# CW308T_ATSAMR21_Micro.net
KiCad netlist of a schematic drawn in Altium Designer
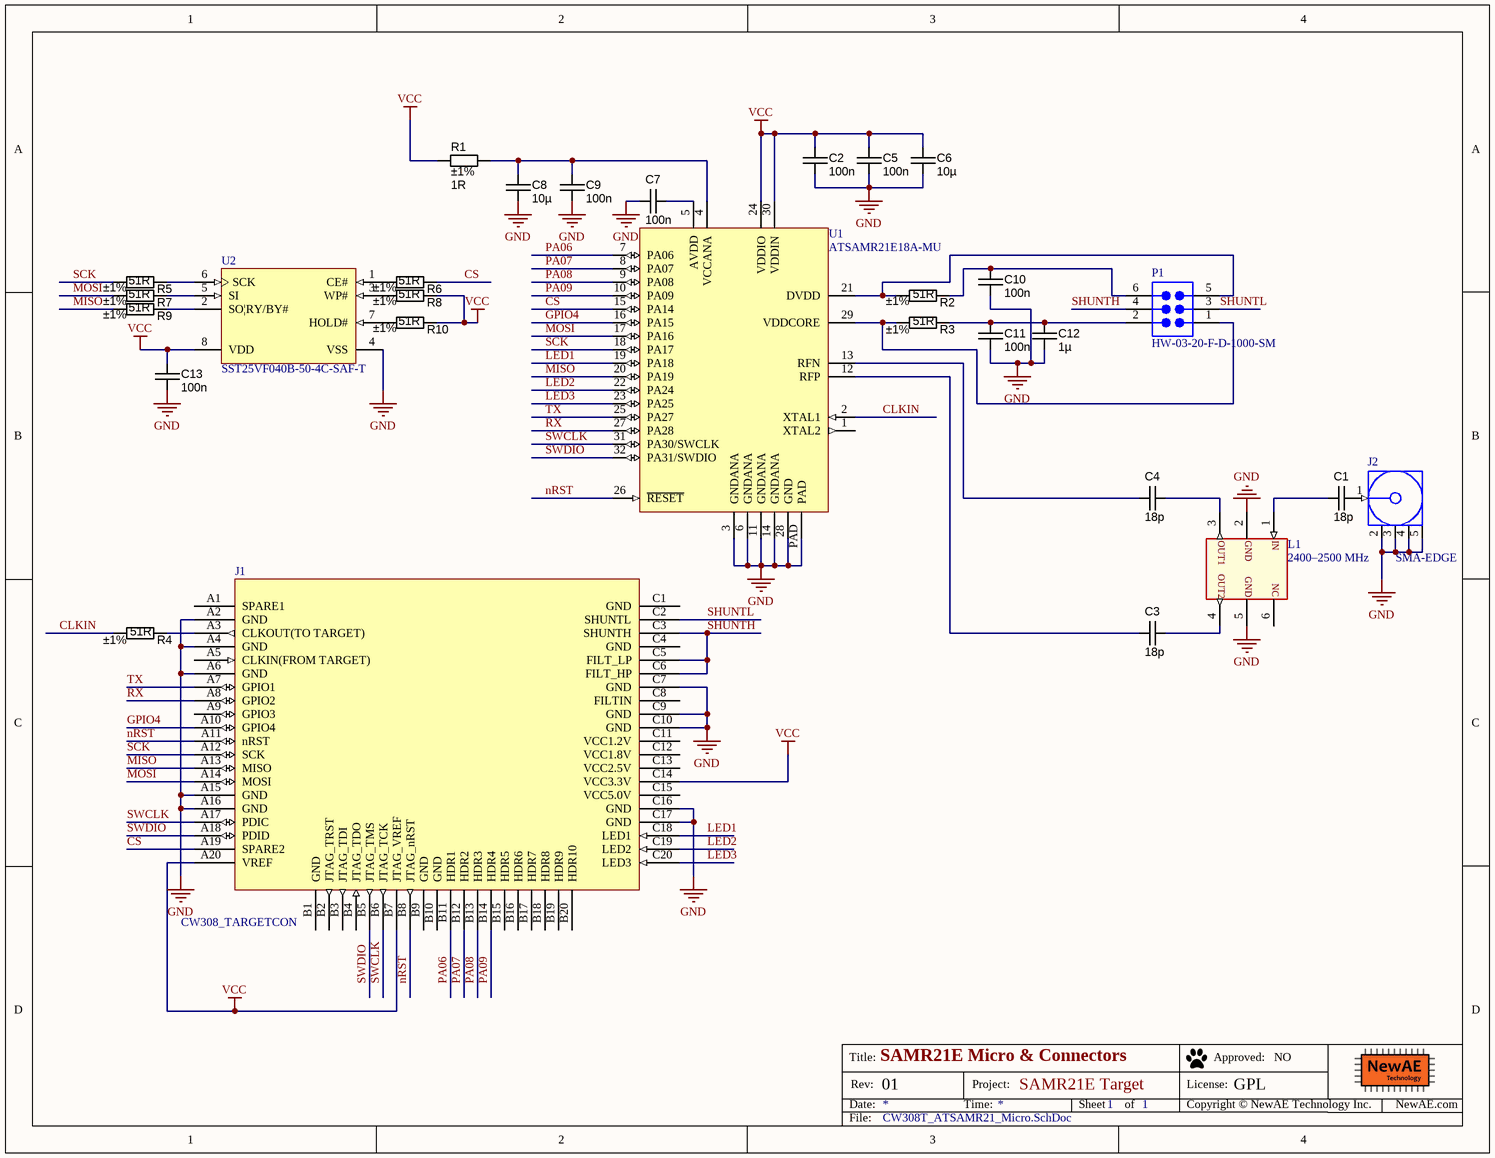
[diagram p0: CW308T_ATSAMR21_Micro.SchDoc]

(export (version "E")
  (design (tool "Eeschema 10.0.6"))
  (components
    (comp (ref "C1")
      (value "18p")
      (footprint "CAPC1608X90N")
      (description "Capacitor SMD Cer 18pF 2% 100V NP0 0603")
      (fields (field (name "TOLERANCE") "±2%"))
      (libsource (lib "PBL - Capacitors") (part "CAPC_18p_0603_100V"))
    )
    (comp (ref "C2")
      (value "100n")
      (footprint "CAPC1608X90N")
      (description "Capacitor SMD Cer 100nF 10% 50V X7R 0603")
      (fields (field (name "TOLERANCE") "±10%") (field (name "Comment") "approved sub OK"))
      (libsource (lib "PBL - Capacitors") (part "CAPC_100n_0603_X7R_50V_10%"))
    )
    (comp (ref "C3")
      (value "18p")
      (footprint "CAPC1608X90N")
      (description "Capacitor SMD Cer 18pF 2% 100V NP0 0603")
      (fields (field (name "TOLERANCE") "±2%"))
      (libsource (lib "PBL - Capacitors") (part "CAPC_18p_0603_100V"))
    )
    (comp (ref "C4")
      (value "18p")
      (footprint "CAPC1608X90N")
      (description "Capacitor SMD Cer 18pF 2% 100V NP0 0603")
      (fields (field (name "TOLERANCE") "±2%"))
      (libsource (lib "PBL - Capacitors") (part "CAPC_18p_0603_100V"))
    )
    (comp (ref "C5")
      (value "100n")
      (footprint "CAPC1608X90N")
      (description "Capacitor SMD Cer 100nF 10% 50V X7R 0603")
      (fields (field (name "TOLERANCE") "±10%") (field (name "Comment") "approved sub OK"))
      (libsource (lib "PBL - Capacitors") (part "CAPC_100n_0603_X7R_50V_10%"))
    )
    (comp (ref "C6")
      (value "10µ")
      (footprint "CAPC1608X90N")
      (description "Capacitor SMD Cer 10uF 10% 10V X5R 0603")
      (fields (field (name "TOLERANCE") "±10%") (field (name "Comment") "approved sub OK"))
      (libsource (lib "PBL - Capacitors") (part "CAPC_10u_0603_6V3"))
    )
    (comp (ref "C7")
      (value "100n")
      (footprint "CAPC1608X90N")
      (description "Capacitor SMD Cer 100nF 10% 50V X7R 0603")
      (fields (field (name "TOLERANCE") "±10%") (field (name "Comment") "approved sub OK"))
      (libsource (lib "PBL - Capacitors") (part "CAPC_100n_0603_X7R_50V_10%"))
    )
    (comp (ref "C8")
      (value "10µ")
      (footprint "CAPC1608X90N")
      (description "Capacitor SMD Cer 10uF 10% 10V X5R 0603")
      (fields (field (name "TOLERANCE") "±10%") (field (name "Comment") "approved sub OK"))
      (libsource (lib "PBL - Capacitors") (part "CAPC_10u_0603_6V3"))
    )
    (comp (ref "C9")
      (value "100n")
      (footprint "CAPC1608X90N")
      (description "Capacitor SMD Cer 100nF 10% 50V X7R 0603")
      (fields (field (name "TOLERANCE") "±10%") (field (name "Comment") "approved sub OK"))
      (libsource (lib "PBL - Capacitors") (part "CAPC_100n_0603_X7R_50V_10%"))
    )
    (comp (ref "C10")
      (value "100n")
      (footprint "CAPC1608X90N")
      (description "Capacitor SMD Cer 100nF 10% 50V X7R 0603")
      (fields (field (name "TOLERANCE") "±10%") (field (name "Comment") "approved sub OK"))
      (libsource (lib "PBL - Capacitors") (part "CAPC_100n_0603_X7R_50V_10%"))
    )
    (comp (ref "C11")
      (value "100n")
      (footprint "CAPC1608X90N")
      (description "Capacitor SMD Cer 100nF 10% 50V X7R 0603")
      (fields (field (name "TOLERANCE") "±10%") (field (name "Comment") "approved sub OK"))
      (libsource (lib "PBL - Capacitors") (part "CAPC_100n_0603_X7R_50V_10%"))
    )
    (comp (ref "C12")
      (value "1µ")
      (footprint "CAPC1608X90N")
      (description "Capacitor SMD Cer 1uF 10% 16V X7R 0603")
      (fields (field (name "TOLERANCE") "±10%") (field (name "Comment") "approved sub OK"))
      (libsource (lib "PBL - Capacitors") (part "CAPC_1u_0603_X7R_16V_10%"))
    )
    (comp (ref "C13")
      (value "100n")
      (footprint "CAPC1608X90N")
      (description "Capacitor SMD Cer 100nF 10% 50V X7R 0603")
      (fields (field (name "TOLERANCE") "±10%") (field (name "Comment") "approved sub OK"))
      (libsource (lib "PBL - Capacitors") (part "CAPC_100n_0603_X7R_50V_10%"))
    )
    (comp (ref "J1")
      (value "CW308_TARGETCON")
      (footprint "ChipWhisperer_AltiumLib:CW308_TBOARD_CONN")
      (description "CW308 \"Standard\" Target Board Connector")
      (libsource (lib "ChipWhisperer_AltiumLib") (part "CW308_TBOARD"))
    )
    (comp (ref "J2")
      (value "SMA-EDGE")
      (footprint "CON-SMAM-PCB-EDGE062")
      (description "SMA Female Edge Mount Connector for 0.062\" Thick Board")
      (libsource (lib "NewAE_AltiumLib") (part "CON-SMA-PCBEDGE-003.062"))
    )
    (comp (ref "L1")
      (value "2400–2500 MHz")
      (footprint "WE-BAL_0603")
      (description "WE-BAL Multilayer Chip Balun, Frequence=2400–2500 MHz")
      (fields
        (field (name "PARTNO") "748411245")
        (field (name "MANUFACTURER") "Wurth Elektronik")
        (field (name "CREATED BY") "Baojun Chen")
      )
      (libsource (lib "Altium_WE-BAL_rev15a") (part "WE-BAL 0603, 748411245"))
    )
    (comp (ref "P1")
      (value "HW-03-20-F-D-1000-SM")
      (footprint "SMTC-HW-03-20-X-D-1000-SM")
      (fields (field (name "MANUFACTURER") "Samtec"))
      (libsource (lib "Altium Content Vault") (part "SMTC-HW-03-20-X-D-X-SM"))
    )
    (comp (ref "R1")
      (value "1R")
      (footprint "RESC1608X55N")
      (description "Resistor SMD chip 1 Ohm 0.1W 1% 0603")
      (fields (field (name "TOLERANCE") "±1%") (field (name "Comment") "Thick Film"))
      (libsource (lib "PBL - Resistors") (part "RES_1R_0603_1%"))
    )
    (comp (ref "R2")
      (value "51R")
      (footprint "RESC1608X55N")
      (description "Resistor SMD chip 51 Ohm 0.1W 1% 0603")
      (fields (field (name "TOLERANCE") "±1%") (field (name "Comment") "Thick Film"))
      (libsource (lib "PBL - Resistors") (part "RES_51R_0603_1%"))
    )
    (comp (ref "R3")
      (value "51R")
      (footprint "RESC1608X55N")
      (description "Resistor SMD chip 51 Ohm 0.1W 1% 0603")
      (fields (field (name "TOLERANCE") "±1%") (field (name "Comment") "Thick Film"))
      (libsource (lib "PBL - Resistors") (part "RES_51R_0603_1%"))
    )
    (comp (ref "R4")
      (value "51R")
      (footprint "RESC1608X55N")
      (description "Resistor SMD chip 51 Ohm 0.1W 1% 0603")
      (fields (field (name "TOLERANCE") "±1%") (field (name "Comment") "Thick Film"))
      (libsource (lib "PBL - Resistors") (part "RES_51R_0603_1%"))
    )
    (comp (ref "R5")
      (value "51R")
      (footprint "RESC1608X55N")
      (description "Resistor SMD chip 51 Ohm 0.1W 1% 0603")
      (fields (field (name "TOLERANCE") "±1%") (field (name "Comment") "Thick Film"))
      (libsource (lib "PBL - Resistors") (part "RES_51R_0603_1%"))
    )
    (comp (ref "R6")
      (value "51R")
      (footprint "RESC1608X55N")
      (description "Resistor SMD chip 51 Ohm 0.1W 1% 0603")
      (fields (field (name "TOLERANCE") "±1%") (field (name "Comment") "Thick Film"))
      (libsource (lib "PBL - Resistors") (part "RES_51R_0603_1%"))
    )
    (comp (ref "R7")
      (value "51R")
      (footprint "RESC1608X55N")
      (description "Resistor SMD chip 51 Ohm 0.1W 1% 0603")
      (fields (field (name "TOLERANCE") "±1%") (field (name "Comment") "Thick Film"))
      (libsource (lib "PBL - Resistors") (part "RES_51R_0603_1%"))
    )
    (comp (ref "R8")
      (value "51R")
      (footprint "RESC1608X55N")
      (description "Resistor SMD chip 51 Ohm 0.1W 1% 0603")
      (fields (field (name "TOLERANCE") "±1%") (field (name "Comment") "Thick Film"))
      (libsource (lib "PBL - Resistors") (part "RES_51R_0603_1%"))
    )
    (comp (ref "R9")
      (value "51R")
      (footprint "RESC1608X55N")
      (description "Resistor SMD chip 51 Ohm 0.1W 1% 0603")
      (fields (field (name "TOLERANCE") "±1%") (field (name "Comment") "Thick Film"))
      (libsource (lib "PBL - Resistors") (part "RES_51R_0603_1%"))
    )
    (comp (ref "R10")
      (value "51R")
      (footprint "RESC1608X55N")
      (description "Resistor SMD chip 51 Ohm 0.1W 1% 0603")
      (fields (field (name "TOLERANCE") "±1%") (field (name "Comment") "Thick Film"))
      (libsource (lib "PBL - Resistors") (part "RES_51R_0603_1%"))
    )
    (comp (ref "U1")
      (value "ATSAMR21E18A-MU")
      (footprint "NewAE_AltiumLib:QFN50P500X500X120_HS-33M")
      (description "Atmel Cortex M0 + 802.15.4 Radio")
      (libsource (lib "NewAE_AltiumLib") (part "ATSAMR21E18A-MU"))
    )
    (comp (ref "U2")
      (value "SST25VF040B-50-4C-SAF-T")
      (footprint "MCHP-SOIC-SA8_N")
      (description "4 Mbit SPI Serial Flash, 2.7 to 3.6 V, 50 MHz, 0 to 70 degC, 8-pin SOIC (SA8), Tape and Reel")
      (fields (field (name "MANUFACTURER") "Microchip"))
      (libsource (lib "Altium Content Vault") (part "MCHP-SST25VFXXXB-SOIX-8"))
    )
  )
  (nets
    (net (code "1") (name "/CLKIN") (class "Default")
      (node (ref "R4") (pin "2") (pinfunction "2_2") (pintype "passive"))
      (node (ref "U1") (pin "2") (pinfunction "XTAL1_2") (pintype "input"))
    )
    (net (code "2") (name "/CS") (class "Default")
      (node (ref "J1") (pin "A19") (pinfunction "SPARE2_A19") (pintype "passive"))
      (node (ref "R6") (pin "1") (pinfunction "1_1") (pintype "passive"))
      (node (ref "U1") (pin "15") (pinfunction "PA14_15") (pintype "bidirectional"))
    )
    (net (code "3") (name "/GPIO4") (class "Default")
      (node (ref "J1") (pin "A10") (pinfunction "GPIO4_A10") (pintype "bidirectional"))
      (node (ref "U1") (pin "16") (pinfunction "PA15_16") (pintype "bidirectional"))
    )
    (net (code "4") (name "/LED1") (class "Default")
      (node (ref "J1") (pin "C18") (pinfunction "LED1_C18") (pintype "input"))
      (node (ref "U1") (pin "19") (pinfunction "PA18_19") (pintype "bidirectional"))
    )
    (net (code "5") (name "/LED2") (class "Default")
      (node (ref "J1") (pin "C19") (pinfunction "LED2_C19") (pintype "input"))
      (node (ref "U1") (pin "22") (pinfunction "PA24_22") (pintype "bidirectional"))
    )
    (net (code "6") (name "/LED3") (class "Default")
      (node (ref "J1") (pin "C20") (pinfunction "LED3_C20") (pintype "input"))
      (node (ref "U1") (pin "23") (pinfunction "PA25_23") (pintype "bidirectional"))
    )
    (net (code "7") (name "/MISO") (class "Default")
      (node (ref "J1") (pin "A13") (pinfunction "MISO_A13") (pintype "bidirectional"))
      (node (ref "R9") (pin "2") (pinfunction "2_2") (pintype "passive"))
      (node (ref "U1") (pin "20") (pinfunction "PA19_20") (pintype "bidirectional"))
    )
    (net (code "8") (name "/MOSI") (class "Default")
      (node (ref "J1") (pin "A14") (pinfunction "MOSI_A14") (pintype "bidirectional"))
      (node (ref "R7") (pin "2") (pinfunction "2_2") (pintype "passive"))
      (node (ref "U1") (pin "17") (pinfunction "PA16_17") (pintype "bidirectional"))
    )
    (net (code "9") (name "/PA06") (class "Default")
      (node (ref "J1") (pin "B11") (pinfunction "HDR1_B11") (pintype "passive"))
      (node (ref "U1") (pin "7") (pinfunction "PA06_7") (pintype "bidirectional"))
    )
    (net (code "10") (name "/PA07") (class "Default")
      (node (ref "J1") (pin "B12") (pinfunction "HDR2_B12") (pintype "passive"))
      (node (ref "U1") (pin "8") (pinfunction "PA07_8") (pintype "bidirectional"))
    )
    (net (code "11") (name "/PA08") (class "Default")
      (node (ref "J1") (pin "B13") (pinfunction "HDR3_B13") (pintype "passive"))
      (node (ref "U1") (pin "9") (pinfunction "PA08_9") (pintype "bidirectional"))
    )
    (net (code "12") (name "/PA09") (class "Default")
      (node (ref "J1") (pin "B14") (pinfunction "HDR4_B14") (pintype "passive"))
      (node (ref "U1") (pin "10") (pinfunction "PA09_10") (pintype "bidirectional"))
    )
    (net (code "13") (name "/RX") (class "Default")
      (node (ref "J1") (pin "A8") (pinfunction "GPIO2_A8") (pintype "bidirectional"))
      (node (ref "U1") (pin "27") (pinfunction "PA28_27") (pintype "bidirectional"))
    )
    (net (code "14") (name "/SCK") (class "Default")
      (node (ref "J1") (pin "A12") (pinfunction "SCK_A12") (pintype "bidirectional"))
      (node (ref "R5") (pin "2") (pinfunction "2_2") (pintype "passive"))
      (node (ref "U1") (pin "18") (pinfunction "PA17_18") (pintype "bidirectional"))
    )
    (net (code "15") (name "/SHUNTH") (class "Default")
      (node (ref "J1") (pin "C3") (pinfunction "SHUNTH_C3") (pintype "passive"))
      (node (ref "J1") (pin "C5") (pinfunction "FILT_LP_C5") (pintype "passive"))
      (node (ref "J1") (pin "C6") (pinfunction "FILT_HP_C6") (pintype "passive"))
      (node (ref "P1") (pin "4") (pinfunction "4_4") (pintype "passive"))
    )
    (net (code "16") (name "/SHUNTL") (class "Default")
      (node (ref "J1") (pin "C2") (pinfunction "SHUNTL_C2") (pintype "passive"))
      (node (ref "P1") (pin "3") (pinfunction "3_3") (pintype "passive"))
    )
    (net (code "17") (name "/SWCLK") (class "Default")
      (node (ref "J1") (pin "A17") (pinfunction "PDIC_A17") (pintype "bidirectional"))
      (node (ref "J1") (pin "B6") (pinfunction "JTAG_TCK_B6") (pintype "output"))
      (node (ref "U1") (pin "31") (pinfunction "PA30/SWCLK_31") (pintype "bidirectional"))
    )
    (net (code "18") (name "/SWDIO") (class "Default")
      (node (ref "J1") (pin "A18") (pinfunction "PDID_A18") (pintype "bidirectional"))
      (node (ref "J1") (pin "B5") (pinfunction "JTAG_TMS_B5") (pintype "output"))
      (node (ref "U1") (pin "32") (pinfunction "PA31/SWDIO_32") (pintype "bidirectional"))
    )
    (net (code "19") (name "/TX") (class "Default")
      (node (ref "J1") (pin "A7") (pinfunction "GPIO1_A7") (pintype "bidirectional"))
      (node (ref "U1") (pin "25") (pinfunction "PA27_25") (pintype "bidirectional"))
    )
    (net (code "20") (name "/nRST") (class "Default")
      (node (ref "J1") (pin "A11") (pinfunction "nRST_A11") (pintype "bidirectional"))
      (node (ref "J1") (pin "B8") (pinfunction "JTAG_nRST_B8") (pintype "output"))
      (node (ref "U1") (pin "26") (pinfunction "~{RESET}_26") (pintype "input"))
    )
    (net (code "21") (name "GND") (class "Default")
      (node (ref "C10") (pin "2") (pintype "passive"))
      (node (ref "C11") (pin "2") (pintype "passive"))
      (node (ref "C12") (pin "2") (pintype "passive"))
      (node (ref "C13") (pin "2") (pintype "passive"))
      (node (ref "C2") (pin "2") (pintype "passive"))
      (node (ref "C5") (pin "2") (pintype "passive"))
      (node (ref "C6") (pin "2") (pintype "passive"))
      (node (ref "C7") (pin "2") (pintype "passive"))
      (node (ref "C8") (pin "2") (pintype "passive"))
      (node (ref "C9") (pin "2") (pintype "passive"))
      (node (ref "J1") (pin "A15") (pinfunction "GND_A15") (pintype "passive"))
      (node (ref "J1") (pin "A16") (pinfunction "GND_A16") (pintype "passive"))
      (node (ref "J1") (pin "A2") (pinfunction "GND_A2") (pintype "passive"))
      (node (ref "J1") (pin "A4") (pinfunction "GND_A4") (pintype "passive"))
      (node (ref "J1") (pin "A6") (pinfunction "GND_A6") (pintype "power_in"))
      (node (ref "J1") (pin "C10") (pinfunction "GND_C10") (pintype "power_in"))
      (node (ref "J1") (pin "C16") (pinfunction "GND_C16") (pintype "power_in"))
      (node (ref "J1") (pin "C17") (pinfunction "GND_C17") (pintype "power_in"))
      (node (ref "J1") (pin "C7") (pinfunction "GND_C7") (pintype "power_in"))
      (node (ref "J1") (pin "C9") (pinfunction "GND_C9") (pintype "power_in"))
      (node (ref "J2") (pin "2") (pinfunction "GND_2") (pintype "power_in"))
      (node (ref "J2") (pin "3") (pinfunction "GND_3") (pintype "power_in"))
      (node (ref "J2") (pin "4") (pinfunction "GND_4") (pintype "power_in"))
      (node (ref "J2") (pin "5") (pinfunction "GND_5") (pintype "power_in"))
      (node (ref "L1") (pin "2") (pinfunction "GND_2") (pintype "passive"))
      (node (ref "L1") (pin "5") (pinfunction "GND_5") (pintype "passive"))
      (node (ref "U1") (pin "11") (pinfunction "GNDANA_11") (pintype "power_in"))
      (node (ref "U1") (pin "14") (pinfunction "GNDANA_14") (pintype "power_in"))
      (node (ref "U1") (pin "28") (pinfunction "GND_28") (pintype "power_in"))
      (node (ref "U1") (pin "3") (pinfunction "GNDANA_3") (pintype "power_in"))
      (node (ref "U1") (pin "6") (pinfunction "GNDANA_6") (pintype "power_in"))
      (node (ref "U1") (pin "PAD") (pinfunction "PAD_PAD") (pintype "power_in"))
      (node (ref "U2") (pin "4") (pinfunction "VSS_4") (pintype "power_in"))
    )
    (net (code "22") (name "Net-(C10-Pad1)") (class "Default")
      (node (ref "C10") (pin "1") (pintype "passive"))
      (node (ref "P1") (pin "6") (pinfunction "6_6") (pintype "passive"))
      (node (ref "R2") (pin "1") (pinfunction "1_1") (pintype "passive"))
    )
    (net (code "23") (name "Net-(C11-Pad1)") (class "Default")
      (node (ref "C11") (pin "1") (pintype "passive"))
      (node (ref "C12") (pin "1") (pintype "passive"))
      (node (ref "P1") (pin "2") (pinfunction "2_2") (pintype "passive"))
      (node (ref "R3") (pin "1") (pinfunction "1_1") (pintype "passive"))
    )
    (net (code "24") (name "Net-(J1-CLKOUT(TO_TARGET))") (class "Default")
      (node (ref "J1") (pin "A3") (pinfunction "CLKOUT(TO_TARGET)_A3") (pintype "output"))
      (node (ref "R4") (pin "1") (pinfunction "1_1") (pintype "passive"))
    )
    (net (code "25") (name "Net-(J2-Signal)") (class "Default")
      (node (ref "C1") (pin "2") (pintype "passive"))
      (node (ref "J2") (pin "1") (pinfunction "Signal_1") (pintype "input"))
    )
    (net (code "26") (name "Net-(L1-IN)") (class "Default")
      (node (ref "C1") (pin "1") (pintype "passive"))
      (node (ref "L1") (pin "1") (pinfunction "IN_1") (pintype "input"))
    )
    (net (code "27") (name "Net-(L1-OUT1)") (class "Default")
      (node (ref "C4") (pin "2") (pintype "passive"))
      (node (ref "L1") (pin "3") (pinfunction "OUT1_3") (pintype "output"))
    )
    (net (code "28") (name "Net-(L1-OUT2)") (class "Default")
      (node (ref "C3") (pin "2") (pintype "passive"))
      (node (ref "L1") (pin "4") (pinfunction "OUT2_4") (pintype "output"))
    )
    (net (code "29") (name "Net-(U1-AVDD)") (class "Default")
      (node (ref "C7") (pin "1") (pintype "passive"))
      (node (ref "U1") (pin "5") (pinfunction "AVDD_5") (pintype "power_in"))
    )
    (net (code "30") (name "Net-(U1-DVDD)") (class "Default")
      (node (ref "P1") (pin "5") (pinfunction "5_5") (pintype "passive"))
      (node (ref "R2") (pin "2") (pinfunction "2_2") (pintype "passive"))
      (node (ref "U1") (pin "21") (pinfunction "DVDD_21") (pintype "power_in"))
    )
    (net (code "31") (name "Net-(U1-RFN)") (class "Default")
      (node (ref "C4") (pin "1") (pintype "passive"))
      (node (ref "U1") (pin "13") (pinfunction "RFN_13") (pintype "passive"))
    )
    (net (code "32") (name "Net-(U1-RFP)") (class "Default")
      (node (ref "C3") (pin "1") (pintype "passive"))
      (node (ref "U1") (pin "12") (pinfunction "RFP_12") (pintype "passive"))
    )
    (net (code "33") (name "Net-(U1-VCCANA)") (class "Default")
      (node (ref "C8") (pin "1") (pintype "passive"))
      (node (ref "C9") (pin "1") (pintype "passive"))
      (node (ref "R1") (pin "2") (pinfunction "2_2") (pintype "passive"))
      (node (ref "U1") (pin "4") (pinfunction "VCCANA_4") (pintype "power_in"))
    )
    (net (code "34") (name "Net-(U1-VDDCORE)") (class "Default")
      (node (ref "P1") (pin "1") (pinfunction "1_1") (pintype "passive"))
      (node (ref "R3") (pin "2") (pinfunction "2_2") (pintype "passive"))
      (node (ref "U1") (pin "29") (pinfunction "VDDCORE_29") (pintype "power_in"))
    )
    (net (code "35") (name "Net-(U2-CE#)") (class "Default")
      (node (ref "R6") (pin "2") (pinfunction "2_2") (pintype "passive"))
      (node (ref "U2") (pin "1") (pinfunction "CE#_1") (pintype "input"))
    )
    (net (code "36") (name "Net-(U2-HOLD#)") (class "Default")
      (node (ref "R10") (pin "2") (pinfunction "2_2") (pintype "passive"))
      (node (ref "U2") (pin "7") (pinfunction "HOLD#_7") (pintype "input"))
    )
    (net (code "37") (name "Net-(U2-SCK)") (class "Default")
      (node (ref "R5") (pin "1") (pinfunction "1_1") (pintype "passive"))
      (node (ref "U2") (pin "6") (pinfunction "SCK_6") (pintype "input"))
    )
    (net (code "38") (name "Net-(U2-SI)") (class "Default")
      (node (ref "R7") (pin "1") (pinfunction "1_1") (pintype "passive"))
      (node (ref "U2") (pin "5") (pinfunction "SI_5") (pintype "input"))
    )
    (net (code "39") (name "Net-(U2-SO¦RY{slash}BY#)") (class "Default")
      (node (ref "R9") (pin "1") (pinfunction "1_1") (pintype "passive"))
      (node (ref "U2") (pin "2") (pinfunction "SO¦RY/BY#_2") (pintype "tri_state"))
    )
    (net (code "40") (name "Net-(U2-WP#)") (class "Default")
      (node (ref "R8") (pin "2") (pinfunction "2_2") (pintype "passive"))
      (node (ref "U2") (pin "3") (pinfunction "WP#_3") (pintype "input"))
    )
    (net (code "41") (name "VCC") (class "Default")
      (node (ref "C13") (pin "1") (pintype "passive"))
      (node (ref "C2") (pin "1") (pintype "passive"))
      (node (ref "C5") (pin "1") (pintype "passive"))
      (node (ref "C6") (pin "1") (pintype "passive"))
      (node (ref "J1") (pin "A20") (pinfunction "VREF_A20") (pintype "tri_state"))
      (node (ref "J1") (pin "B7") (pinfunction "JTAG_VREF_B7") (pintype "tri_state"))
      (node (ref "J1") (pin "C14") (pinfunction "VCC3.3V_C14") (pintype "power_in"))
      (node (ref "R1") (pin "1") (pinfunction "1_1") (pintype "passive"))
      (node (ref "R10") (pin "1") (pinfunction "1_1") (pintype "passive"))
      (node (ref "R8") (pin "1") (pinfunction "1_1") (pintype "passive"))
      (node (ref "U1") (pin "24") (pinfunction "VDDIO_24") (pintype "power_in"))
      (node (ref "U1") (pin "30") (pinfunction "VDDIN_30") (pintype "power_in"))
      (node (ref "U2") (pin "8") (pinfunction "VDD_8") (pintype "power_in"))
    )
    (net (code "42") (name "unconnected-(J1-CLKIN(FROM_TARGET)-PadA5)") (class "Default")
      (node (ref "J1") (pin "A5") (pinfunction "CLKIN(FROM_TARGET)_A5") (pintype "input"))
    )
    (net (code "43") (name "unconnected-(J1-FILTIN-PadC8)") (class "Default")
      (node (ref "J1") (pin "C8") (pinfunction "FILTIN_C8") (pintype "passive"))
    )
    (net (code "44") (name "unconnected-(J1-GND-PadB1)") (class "Default")
      (node (ref "J1") (pin "B1") (pinfunction "GND_B1") (pintype "passive"))
    )
    (net (code "45") (name "unconnected-(J1-GND-PadB9)") (class "Default")
      (node (ref "J1") (pin "B9") (pinfunction "GND_B9") (pintype "passive"))
    )
    (net (code "46") (name "unconnected-(J1-GND-PadB10)") (class "Default")
      (node (ref "J1") (pin "B10") (pinfunction "GND_B10") (pintype "passive"))
    )
    (net (code "47") (name "unconnected-(J1-GND-PadC1)") (class "Default")
      (node (ref "J1") (pin "C1") (pinfunction "GND_C1") (pintype "power_in"))
    )
    (net (code "48") (name "unconnected-(J1-GND-PadC4)") (class "Default")
      (node (ref "J1") (pin "C4") (pinfunction "GND_C4") (pintype "power_in"))
    )
    (net (code "49") (name "unconnected-(J1-GPIO3-PadA9)") (class "Default")
      (node (ref "J1") (pin "A9") (pinfunction "GPIO3_A9") (pintype "bidirectional"))
    )
    (net (code "50") (name "unconnected-(J1-HDR5-PadB15)") (class "Default")
      (node (ref "J1") (pin "B15") (pinfunction "HDR5_B15") (pintype "passive"))
    )
    (net (code "51") (name "unconnected-(J1-HDR6-PadB16)") (class "Default")
      (node (ref "J1") (pin "B16") (pinfunction "HDR6_B16") (pintype "passive"))
    )
    (net (code "52") (name "unconnected-(J1-HDR7-PadB17)") (class "Default")
      (node (ref "J1") (pin "B17") (pinfunction "HDR7_B17") (pintype "passive"))
    )
    (net (code "53") (name "unconnected-(J1-HDR8-PadB18)") (class "Default")
      (node (ref "J1") (pin "B18") (pinfunction "HDR8_B18") (pintype "passive"))
    )
    (net (code "54") (name "unconnected-(J1-HDR9-PadB19)") (class "Default")
      (node (ref "J1") (pin "B19") (pinfunction "HDR9_B19") (pintype "passive"))
    )
    (net (code "55") (name "unconnected-(J1-HDR10-PadB20)") (class "Default")
      (node (ref "J1") (pin "B20") (pinfunction "HDR10_B20") (pintype "passive"))
    )
    (net (code "56") (name "unconnected-(J1-JTAG_TDI-PadB3)") (class "Default")
      (node (ref "J1") (pin "B3") (pinfunction "JTAG_TDI_B3") (pintype "output"))
    )
    (net (code "57") (name "unconnected-(J1-JTAG_TDO-PadB4)") (class "Default")
      (node (ref "J1") (pin "B4") (pinfunction "JTAG_TDO_B4") (pintype "input"))
    )
    (net (code "58") (name "unconnected-(J1-JTAG_TRST-PadB2)") (class "Default")
      (node (ref "J1") (pin "B2") (pinfunction "JTAG_TRST_B2") (pintype "output"))
    )
    (net (code "59") (name "unconnected-(J1-SPARE1-PadA1)") (class "Default")
      (node (ref "J1") (pin "A1") (pinfunction "SPARE1_A1") (pintype "passive"))
    )
    (net (code "60") (name "unconnected-(J1-VCC1.2V-PadC11)") (class "Default")
      (node (ref "J1") (pin "C11") (pinfunction "VCC1.2V_C11") (pintype "power_in"))
    )
    (net (code "61") (name "unconnected-(J1-VCC1.8V-PadC12)") (class "Default")
      (node (ref "J1") (pin "C12") (pinfunction "VCC1.8V_C12") (pintype "power_in"))
    )
    (net (code "62") (name "unconnected-(J1-VCC2.5V-PadC13)") (class "Default")
      (node (ref "J1") (pin "C13") (pinfunction "VCC2.5V_C13") (pintype "power_in"))
    )
    (net (code "63") (name "unconnected-(J1-VCC5.0V-PadC15)") (class "Default")
      (node (ref "J1") (pin "C15") (pinfunction "VCC5.0V_C15") (pintype "power_in"))
    )
    (net (code "64") (name "unconnected-(L1-NC-Pad6)") (class "Default")
      (node (ref "L1") (pin "6") (pinfunction "NC_6") (pintype "passive"))
    )
    (net (code "65") (name "unconnected-(U1-XTAL2-Pad1)") (class "Default")
      (node (ref "U1") (pin "1") (pinfunction "XTAL2_1") (pintype "output"))
    )
  )
)
